# memory.net
KiCad netlist of a schematic drawn in Altium Designer
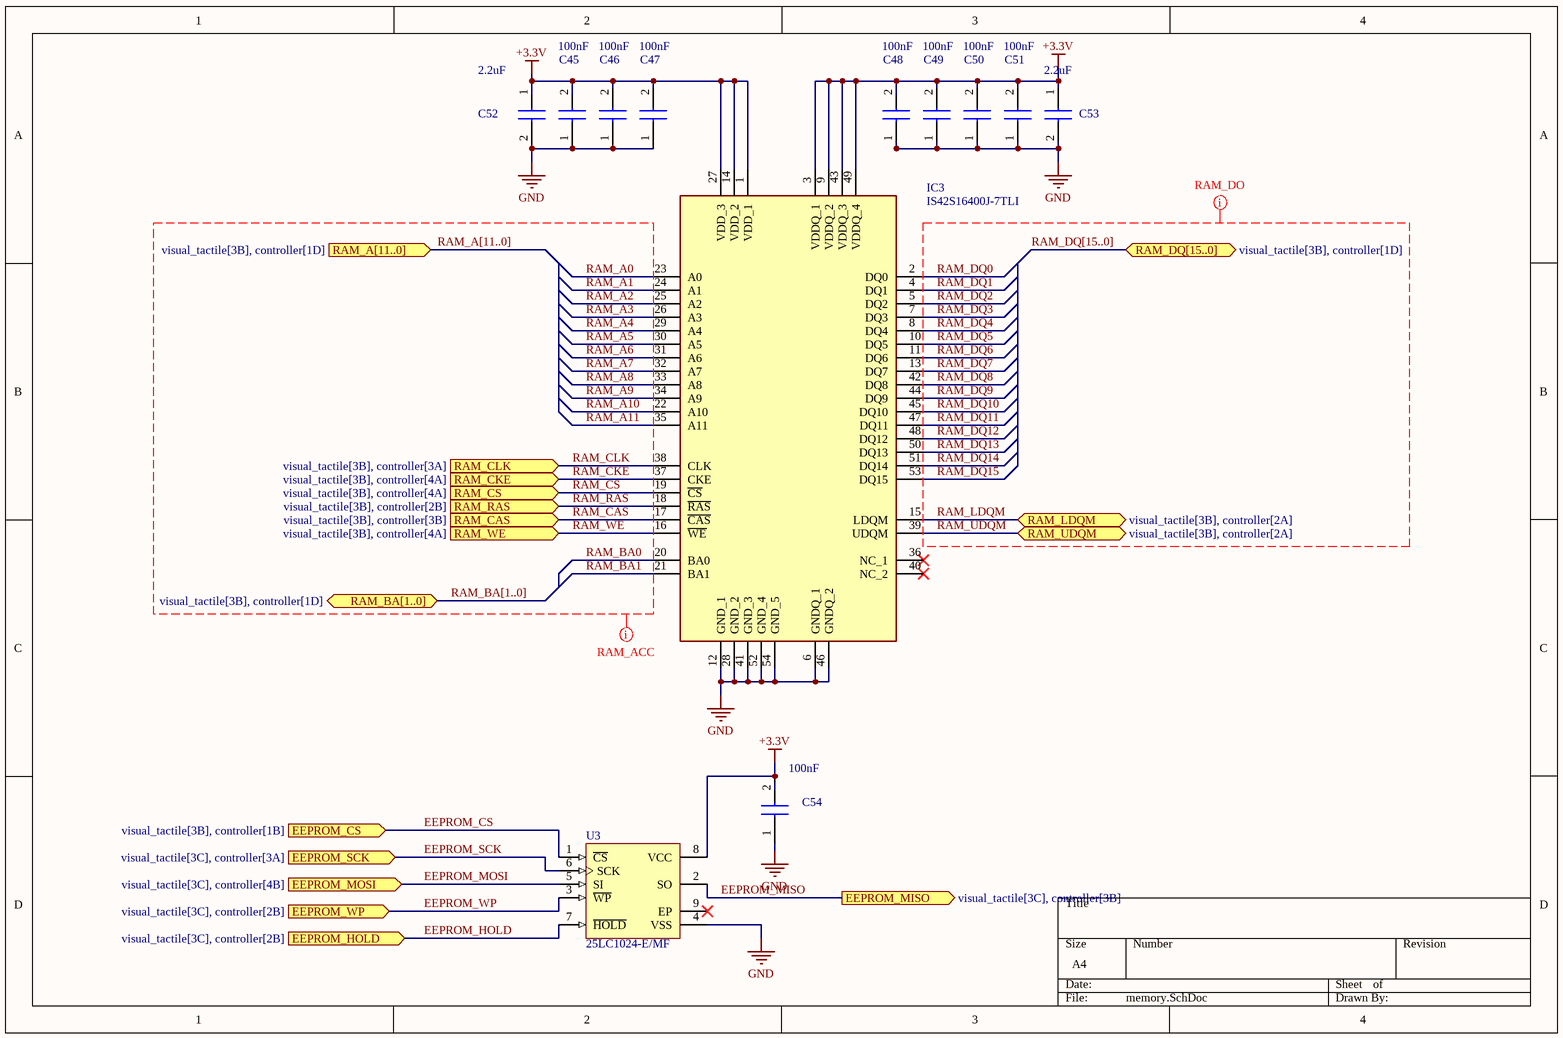
[diagram p0: memory.SchDoc]

(export (version "E")
  (design (tool "Eeschema 10.0.6"))
  (components
    (comp (ref "C45")
      (value "100nF")
      (footprint "PCB_library:CAPC1608X87N")
      (fields
        (field (name "MANUFACTURER_PART_NUMBER") "C0603C300J5GACTU")
        (field (name "MOUSER PART NUMBER") "80-C0603C300J5G")
        (field (name "MANUFACTURER") "TDK")
      )
      (libsource (lib "PCB_library") (part "C0603C300J5GACTU"))
    )
    (comp (ref "C46")
      (value "100nF")
      (footprint "PCB_library:CAPC1608X87N")
      (fields
        (field (name "MANUFACTURER_PART_NUMBER") "C0603C300J5GACTU")
        (field (name "MOUSER PART NUMBER") "80-C0603C300J5G")
        (field (name "MANUFACTURER") "TDK")
      )
      (libsource (lib "PCB_library") (part "C0603C300J5GACTU"))
    )
    (comp (ref "C47")
      (value "100nF")
      (footprint "PCB_library:CAPC1608X87N")
      (fields
        (field (name "MANUFACTURER_PART_NUMBER") "C0603C300J5GACTU")
        (field (name "MOUSER PART NUMBER") "80-C0603C300J5G")
        (field (name "MANUFACTURER") "TDK")
      )
      (libsource (lib "PCB_library") (part "C0603C300J5GACTU"))
    )
    (comp (ref "C48")
      (value "100nF")
      (footprint "PCB_library:CAPC1608X87N")
      (fields
        (field (name "MANUFACTURER_PART_NUMBER") "C0603C300J5GACTU")
        (field (name "MOUSER PART NUMBER") "80-C0603C300J5G")
        (field (name "MANUFACTURER") "TDK")
      )
      (libsource (lib "PCB_library") (part "C0603C300J5GACTU"))
    )
    (comp (ref "C49")
      (value "100nF")
      (footprint "PCB_library:CAPC1608X87N")
      (fields
        (field (name "MANUFACTURER_PART_NUMBER") "C0603C300J5GACTU")
        (field (name "MOUSER PART NUMBER") "80-C0603C300J5G")
        (field (name "MANUFACTURER") "TDK")
      )
      (libsource (lib "PCB_library") (part "C0603C300J5GACTU"))
    )
    (comp (ref "C50")
      (value "100nF")
      (footprint "PCB_library:CAPC1608X87N")
      (fields
        (field (name "MANUFACTURER_PART_NUMBER") "C0603C300J5GACTU")
        (field (name "MOUSER PART NUMBER") "80-C0603C300J5G")
        (field (name "MANUFACTURER") "TDK")
      )
      (libsource (lib "PCB_library") (part "C0603C300J5GACTU"))
    )
    (comp (ref "C51")
      (value "100nF")
      (footprint "PCB_library:CAPC1608X87N")
      (fields
        (field (name "MANUFACTURER_PART_NUMBER") "C0603C300J5GACTU")
        (field (name "MOUSER PART NUMBER") "80-C0603C300J5G")
        (field (name "MANUFACTURER") "TDK")
      )
      (libsource (lib "PCB_library") (part "C0603C300J5GACTU"))
    )
    (comp (ref "C52")
      (value "2.2uF")
      (footprint "PCB_library:CAPC1608X87N")
      (fields
        (field (name "MANUFACTURER_PART_NUMBER") "C0603C300J5GACTU")
        (field (name "MOUSER PART NUMBER") "80-C0603C300J5G")
        (field (name "MANUFACTURER") "KEMET")
      )
      (libsource (lib "PCB_library") (part "C0603C300J5GACTU"))
    )
    (comp (ref "C53")
      (value "2.2uF")
      (footprint "PCB_library:CAPC1608X87N")
      (fields
        (field (name "MANUFACTURER_PART_NUMBER") "C0603C300J5GACTU")
        (field (name "MOUSER PART NUMBER") "80-C0603C300J5G")
        (field (name "MANUFACTURER") "KEMET")
      )
      (libsource (lib "PCB_library") (part "C0603C300J5GACTU"))
    )
    (comp (ref "C54")
      (value "100nF")
      (footprint "PCB_library:CAPC1608X87N")
      (fields
        (field (name "MANUFACTURER_PART_NUMBER") "C0603C300J5GACTU")
        (field (name "MOUSER PART NUMBER") "80-C0603C300J5G")
        (field (name "MANUFACTURER") "TDK")
      )
      (libsource (lib "PCB_library") (part "C0603C300J5GACTU"))
    )
    (comp (ref "IC3")
      (value "IS42S16400J-7TLI")
      (footprint "PCB_library:SOP80P1176X120-54N")
      (description "Integrated Circuit")
      (fields (field (name "MOUSER PART NUMBER") "870-IS42S16400J-7TLI"))
      (libsource (lib "PCB_library") (part "IS42S16400J-7TLI"))
    )
    (comp (ref "U3")
      (value "25LC1024-E/MF")
      (footprint "DFNS-MF8")
      (description "1 Mbit SPI Bus Serial EEPROM, 8-Pin DFN, Extended Temperature")
      (libsource (lib "Altium Content Vault") (part "MEM-SEEPROM-25AA1024-9"))
    )
  )
  (nets
    (net (code "1") (name "+3.3V") (class "Default")
      (node (ref "C45") (pin "2") (pinfunction "2_2") (pintype "passive"))
      (node (ref "C46") (pin "2") (pinfunction "2_2") (pintype "passive"))
      (node (ref "C47") (pin "2") (pinfunction "2_2") (pintype "passive"))
      (node (ref "C48") (pin "2") (pinfunction "2_2") (pintype "passive"))
      (node (ref "C49") (pin "2") (pinfunction "2_2") (pintype "passive"))
      (node (ref "C50") (pin "2") (pinfunction "2_2") (pintype "passive"))
      (node (ref "C51") (pin "2") (pinfunction "2_2") (pintype "passive"))
      (node (ref "C52") (pin "1") (pinfunction "1_1") (pintype "passive"))
      (node (ref "C53") (pin "1") (pinfunction "1_1") (pintype "passive"))
      (node (ref "C54") (pin "2") (pinfunction "2_2") (pintype "passive"))
      (node (ref "IC3") (pin "1") (pinfunction "VDD_1_1") (pintype "passive"))
      (node (ref "IC3") (pin "14") (pinfunction "VDD_2_14") (pintype "passive"))
      (node (ref "IC3") (pin "27") (pinfunction "VDD_3_27") (pintype "passive"))
      (node (ref "IC3") (pin "3") (pinfunction "VDDQ_1_3") (pintype "passive"))
      (node (ref "IC3") (pin "43") (pinfunction "VDDQ_3_43") (pintype "passive"))
      (node (ref "IC3") (pin "49") (pinfunction "VDDQ_4_49") (pintype "passive"))
      (node (ref "IC3") (pin "9") (pinfunction "VDDQ_2_9") (pintype "passive"))
      (node (ref "U3") (pin "8") (pinfunction "VCC_8") (pintype "power_in"))
    )
    (net (code "3") (name "/EEPROM_CS") (class "Default")
      (node (ref "U3") (pin "1") (pinfunction "~{CS}_1") (pintype "input"))
    )
    (net (code "4") (name "/EEPROM_HOLD") (class "Default")
      (node (ref "U3") (pin "7") (pinfunction "~{HOLD}_7") (pintype "input"))
    )
    (net (code "5") (name "/EEPROM_MISO") (class "Default")
      (node (ref "U3") (pin "2") (pinfunction "SO_2") (pintype "tri_state"))
    )
    (net (code "6") (name "/EEPROM_MOSI") (class "Default")
      (node (ref "U3") (pin "5") (pinfunction "SI_5") (pintype "input"))
    )
    (net (code "7") (name "/EEPROM_SCK") (class "Default")
      (node (ref "U3") (pin "6") (pinfunction "SCK_6") (pintype "input"))
    )
    (net (code "8") (name "/EEPROM_WP") (class "Default")
      (node (ref "U3") (pin "3") (pinfunction "~{WP}_3") (pintype "input"))
    )
    (net (code "9") (name "/RAM_A0") (class "Default")
      (node (ref "IC3") (pin "23") (pinfunction "A0_23") (pintype "passive"))
    )
    (net (code "10") (name "/RAM_A1") (class "Default")
      (node (ref "IC3") (pin "24") (pinfunction "A1_24") (pintype "passive"))
    )
    (net (code "11") (name "/RAM_A2") (class "Default")
      (node (ref "IC3") (pin "25") (pinfunction "A2_25") (pintype "passive"))
    )
    (net (code "12") (name "/RAM_A3") (class "Default")
      (node (ref "IC3") (pin "26") (pinfunction "A3_26") (pintype "passive"))
    )
    (net (code "13") (name "/RAM_A4") (class "Default")
      (node (ref "IC3") (pin "29") (pinfunction "A4_29") (pintype "passive"))
    )
    (net (code "14") (name "/RAM_A5") (class "Default")
      (node (ref "IC3") (pin "30") (pinfunction "A5_30") (pintype "passive"))
    )
    (net (code "15") (name "/RAM_A6") (class "Default")
      (node (ref "IC3") (pin "31") (pinfunction "A6_31") (pintype "passive"))
    )
    (net (code "16") (name "/RAM_A7") (class "Default")
      (node (ref "IC3") (pin "32") (pinfunction "A7_32") (pintype "passive"))
    )
    (net (code "17") (name "/RAM_A8") (class "Default")
      (node (ref "IC3") (pin "33") (pinfunction "A8_33") (pintype "passive"))
    )
    (net (code "18") (name "/RAM_A9") (class "Default")
      (node (ref "IC3") (pin "34") (pinfunction "A9_34") (pintype "passive"))
    )
    (net (code "19") (name "/RAM_A10") (class "Default")
      (node (ref "IC3") (pin "22") (pinfunction "A10_22") (pintype "passive"))
    )
    (net (code "20") (name "/RAM_A11") (class "Default")
      (node (ref "IC3") (pin "35") (pinfunction "A11_35") (pintype "passive"))
    )
    (net (code "22") (name "/RAM_BA0") (class "Default")
      (node (ref "IC3") (pin "20") (pinfunction "BA0_20") (pintype "passive"))
    )
    (net (code "23") (name "/RAM_BA1") (class "Default")
      (node (ref "IC3") (pin "21") (pinfunction "BA1_21") (pintype "passive"))
    )
    (net (code "25") (name "/RAM_CAS") (class "Default")
      (node (ref "IC3") (pin "17") (pinfunction "~{CAS}_17") (pintype "passive"))
    )
    (net (code "26") (name "/RAM_CKE") (class "Default")
      (node (ref "IC3") (pin "37") (pinfunction "CKE_37") (pintype "passive"))
    )
    (net (code "27") (name "/RAM_CLK") (class "Default")
      (node (ref "IC3") (pin "38") (pinfunction "CLK_38") (pintype "passive"))
    )
    (net (code "28") (name "/RAM_CS") (class "Default")
      (node (ref "IC3") (pin "19") (pinfunction "~{CS}_19") (pintype "passive"))
    )
    (net (code "29") (name "/RAM_DQ0") (class "Default")
      (node (ref "IC3") (pin "2") (pinfunction "DQ0_2") (pintype "passive"))
    )
    (net (code "30") (name "/RAM_DQ1") (class "Default")
      (node (ref "IC3") (pin "4") (pinfunction "DQ1_4") (pintype "passive"))
    )
    (net (code "31") (name "/RAM_DQ2") (class "Default")
      (node (ref "IC3") (pin "5") (pinfunction "DQ2_5") (pintype "passive"))
    )
    (net (code "32") (name "/RAM_DQ3") (class "Default")
      (node (ref "IC3") (pin "7") (pinfunction "DQ3_7") (pintype "passive"))
    )
    (net (code "33") (name "/RAM_DQ4") (class "Default")
      (node (ref "IC3") (pin "8") (pinfunction "DQ4_8") (pintype "passive"))
    )
    (net (code "34") (name "/RAM_DQ5") (class "Default")
      (node (ref "IC3") (pin "10") (pinfunction "DQ5_10") (pintype "passive"))
    )
    (net (code "35") (name "/RAM_DQ6") (class "Default")
      (node (ref "IC3") (pin "11") (pinfunction "DQ6_11") (pintype "passive"))
    )
    (net (code "36") (name "/RAM_DQ7") (class "Default")
      (node (ref "IC3") (pin "13") (pinfunction "DQ7_13") (pintype "passive"))
    )
    (net (code "37") (name "/RAM_DQ8") (class "Default")
      (node (ref "IC3") (pin "42") (pinfunction "DQ8_42") (pintype "passive"))
    )
    (net (code "38") (name "/RAM_DQ9") (class "Default")
      (node (ref "IC3") (pin "44") (pinfunction "DQ9_44") (pintype "passive"))
    )
    (net (code "39") (name "/RAM_DQ10") (class "Default")
      (node (ref "IC3") (pin "45") (pinfunction "DQ10_45") (pintype "passive"))
    )
    (net (code "40") (name "/RAM_DQ11") (class "Default")
      (node (ref "IC3") (pin "47") (pinfunction "DQ11_47") (pintype "passive"))
    )
    (net (code "41") (name "/RAM_DQ12") (class "Default")
      (node (ref "IC3") (pin "48") (pinfunction "DQ12_48") (pintype "passive"))
    )
    (net (code "42") (name "/RAM_DQ13") (class "Default")
      (node (ref "IC3") (pin "50") (pinfunction "DQ13_50") (pintype "passive"))
    )
    (net (code "43") (name "/RAM_DQ14") (class "Default")
      (node (ref "IC3") (pin "51") (pinfunction "DQ14_51") (pintype "passive"))
    )
    (net (code "44") (name "/RAM_DQ15") (class "Default")
      (node (ref "IC3") (pin "53") (pinfunction "DQ15_53") (pintype "passive"))
    )
    (net (code "46") (name "/RAM_LDQM") (class "Default")
      (node (ref "IC3") (pin "15") (pinfunction "LDQM_15") (pintype "passive"))
    )
    (net (code "47") (name "/RAM_RAS") (class "Default")
      (node (ref "IC3") (pin "18") (pinfunction "~{RAS}_18") (pintype "passive"))
    )
    (net (code "48") (name "/RAM_UDQM") (class "Default")
      (node (ref "IC3") (pin "39") (pinfunction "UDQM_39") (pintype "passive"))
    )
    (net (code "49") (name "/RAM_WE") (class "Default")
      (node (ref "IC3") (pin "16") (pinfunction "~{WE}_16") (pintype "passive"))
    )
    (net (code "50") (name "GND") (class "Default")
      (node (ref "C45") (pin "1") (pinfunction "1_1") (pintype "passive"))
      (node (ref "C46") (pin "1") (pinfunction "1_1") (pintype "passive"))
      (node (ref "C47") (pin "1") (pinfunction "1_1") (pintype "passive"))
      (node (ref "C48") (pin "1") (pinfunction "1_1") (pintype "passive"))
      (node (ref "C49") (pin "1") (pinfunction "1_1") (pintype "passive"))
      (node (ref "C50") (pin "1") (pinfunction "1_1") (pintype "passive"))
      (node (ref "C51") (pin "1") (pinfunction "1_1") (pintype "passive"))
      (node (ref "C52") (pin "2") (pinfunction "2_2") (pintype "passive"))
      (node (ref "C53") (pin "2") (pinfunction "2_2") (pintype "passive"))
      (node (ref "C54") (pin "1") (pinfunction "1_1") (pintype "passive"))
      (node (ref "IC3") (pin "12") (pinfunction "GND_1_12") (pintype "passive"))
      (node (ref "IC3") (pin "28") (pinfunction "GND_2_28") (pintype "passive"))
      (node (ref "IC3") (pin "41") (pinfunction "GND_3_41") (pintype "passive"))
      (node (ref "IC3") (pin "46") (pinfunction "GNDQ_2_46") (pintype "passive"))
      (node (ref "IC3") (pin "52") (pinfunction "GND_4_52") (pintype "passive"))
      (node (ref "IC3") (pin "54") (pinfunction "GND_5_54") (pintype "passive"))
      (node (ref "IC3") (pin "6") (pinfunction "GNDQ_1_6") (pintype "passive"))
      (node (ref "U3") (pin "4") (pinfunction "VSS_4") (pintype "power_in"))
    )
    (net (code "51") (name "unconnected-(IC3-NC_1-Pad36)") (class "Default")
      (node (ref "IC3") (pin "36") (pinfunction "NC_1_36") (pintype "passive+no_connect"))
    )
    (net (code "52") (name "unconnected-(IC3-NC_2-Pad40)") (class "Default")
      (node (ref "IC3") (pin "40") (pinfunction "NC_2_40") (pintype "passive+no_connect"))
    )
    (net (code "53") (name "unconnected-(U3-EP-Pad9)") (class "Default")
      (node (ref "U3") (pin "9") (pinfunction "EP_9") (pintype "passive+no_connect"))
    )
  )
)
